# Ingresso_1_1SchDoc.net
KiCad netlist of a schematic drawn in Altium Designer
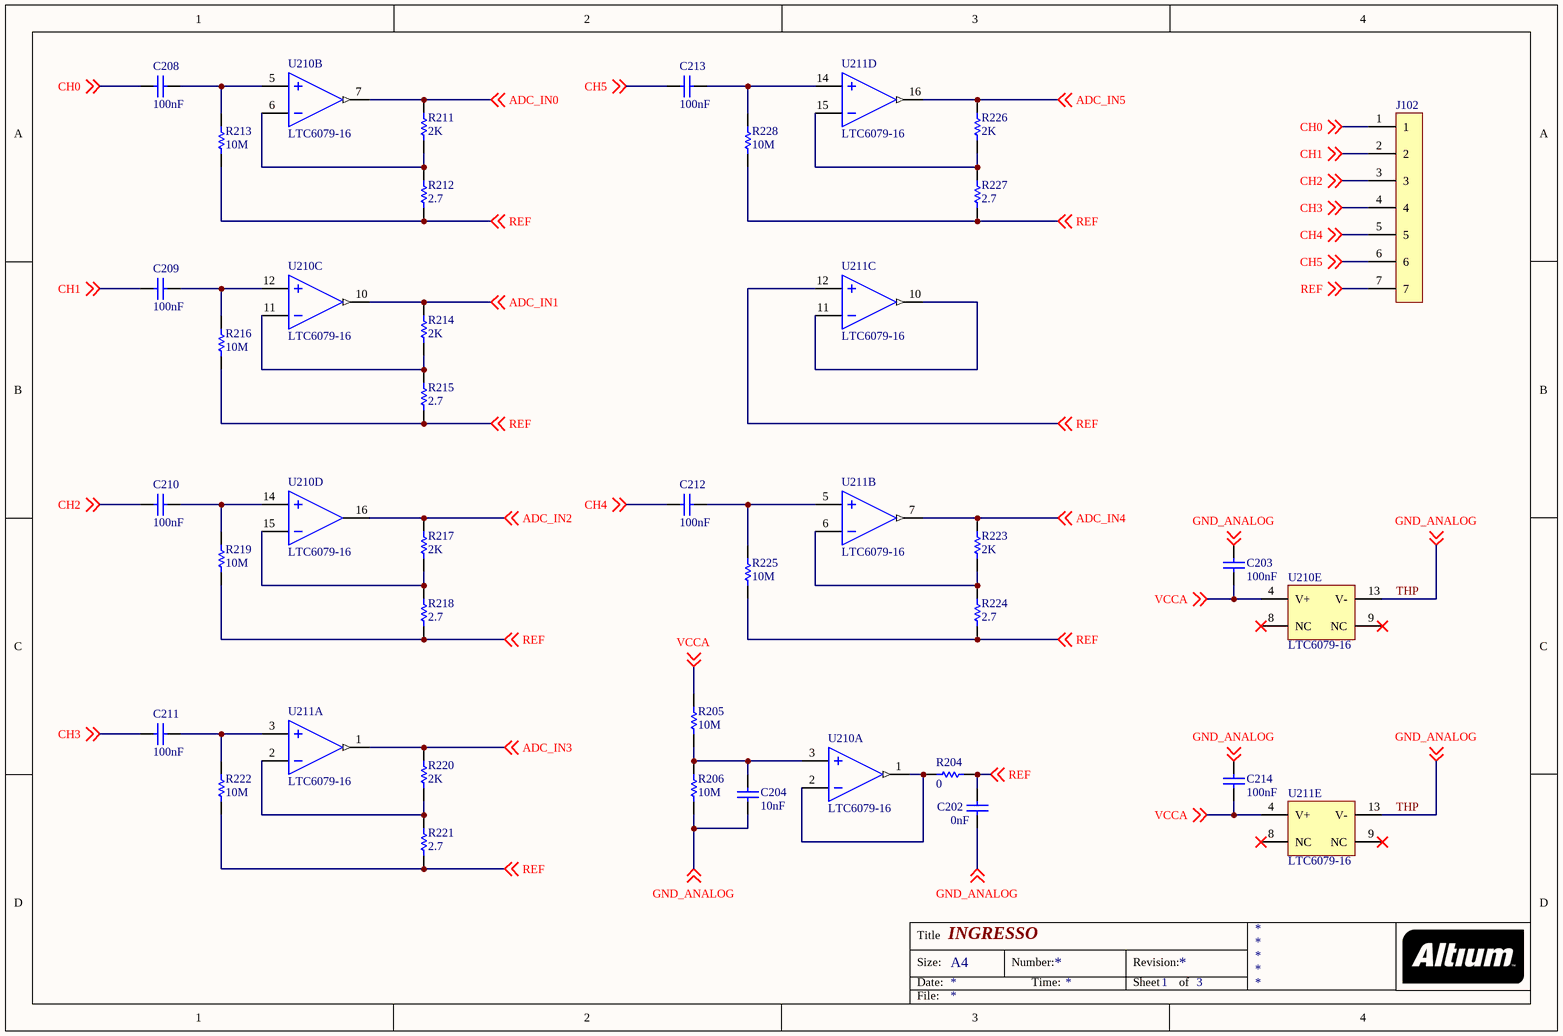
[diagram p0: Ingresso_1.1SchDoc.SchDoc]

(export (version "E")
  (design (tool "Eeschema 10.0.6"))
  (components
    (comp (ref "C202")
      (value "0nF")
      (footprint "Footprint:0402 Capacitor")
      (description "Capacitor SMD 0402")
      (fields
        (field (name "MANUFACTURER") "MULTICOMP")
        (field (name "MANUFACTURER PART NUMBER") "MC0402X104M160CT")
        (field (name "PUBLISHER") "Altium Limited")
      )
      (libsource (lib "Capacitor") (part "Cap SMD"))
    )
    (comp (ref "C203")
      (value "100nF")
      (footprint "Footprint:0402 Capacitor")
      (description "Capacitor SMD 0402")
      (fields
        (field (name "MANUFACTURER") "MULTICOMP")
        (field (name "MANUFACTURER PART NUMBER") "MC0402X104M160CT")
        (field (name "PUBLISHER") "Altium Limited")
      )
      (libsource (lib "Capacitor") (part "Cap SMD"))
    )
    (comp (ref "C204")
      (value "10nF")
      (footprint "Footprint:0402 Capacitor")
      (description "Capacitor SMD 0402")
      (fields
        (field (name "MANUFACTURER") "MULTICOMP")
        (field (name "MANUFACTURER PART NUMBER") "MC0402X104M160CT")
        (field (name "PUBLISHER") "Altium Limited")
      )
      (libsource (lib "Capacitor") (part "Cap SMD"))
    )
    (comp (ref "C208")
      (value "100nF")
      (footprint "Footprint:0402 Capacitor")
      (description "Capacitor SMD 0402")
      (fields
        (field (name "MANUFACTURER") "MULTICOMP")
        (field (name "MANUFACTURER PART NUMBER") "MC0402X104M160CT")
        (field (name "PUBLISHER") "Altium Limited")
      )
      (libsource (lib "Capacitor") (part "Cap SMD"))
    )
    (comp (ref "C209")
      (value "100nF")
      (footprint "Footprint:0402 Capacitor")
      (description "Capacitor SMD 0402")
      (fields
        (field (name "MANUFACTURER") "MULTICOMP")
        (field (name "MANUFACTURER PART NUMBER") "MC0402X104M160CT")
        (field (name "PUBLISHER") "Altium Limited")
      )
      (libsource (lib "Capacitor") (part "Cap SMD"))
    )
    (comp (ref "C210")
      (value "100nF")
      (footprint "Footprint:0402 Capacitor")
      (description "Capacitor SMD 0402")
      (fields
        (field (name "MANUFACTURER") "MULTICOMP")
        (field (name "MANUFACTURER PART NUMBER") "MC0402X104M160CT")
        (field (name "PUBLISHER") "Altium Limited")
      )
      (libsource (lib "Capacitor") (part "Cap SMD"))
    )
    (comp (ref "C211")
      (value "100nF")
      (footprint "Footprint:0402 Capacitor")
      (description "Capacitor SMD 0402")
      (fields
        (field (name "MANUFACTURER") "MULTICOMP")
        (field (name "MANUFACTURER PART NUMBER") "MC0402X104M160CT")
        (field (name "PUBLISHER") "Altium Limited")
      )
      (libsource (lib "Capacitor") (part "Cap SMD"))
    )
    (comp (ref "C212")
      (value "100nF")
      (footprint "Footprint:0402 Capacitor")
      (description "Capacitor SMD 0402")
      (fields
        (field (name "MANUFACTURER") "MULTICOMP")
        (field (name "MANUFACTURER PART NUMBER") "MC0402X104M160CT")
        (field (name "PUBLISHER") "Altium Limited")
      )
      (libsource (lib "Capacitor") (part "Cap SMD"))
    )
    (comp (ref "C213")
      (value "100nF")
      (footprint "Footprint:0402 Capacitor")
      (description "Capacitor SMD 0402")
      (fields
        (field (name "MANUFACTURER") "MULTICOMP")
        (field (name "MANUFACTURER PART NUMBER") "MC0402X104M160CT")
        (field (name "PUBLISHER") "Altium Limited")
      )
      (libsource (lib "Capacitor") (part "Cap SMD"))
    )
    (comp (ref "C214")
      (value "100nF")
      (footprint "Footprint:0402 Capacitor")
      (description "Capacitor SMD 0402")
      (fields
        (field (name "MANUFACTURER") "MULTICOMP")
        (field (name "MANUFACTURER PART NUMBER") "MC0402X104M160CT")
        (field (name "PUBLISHER") "Altium Limited")
      )
      (libsource (lib "Capacitor") (part "Cap SMD"))
    )
    (comp (ref "J102")
      (value "HEADER 1X7")
      (footprint "Footprint:HEADER 1X7")
      (description "Inductor")
      (fields (field (name "PUBLISHER") "Altium Limited"))
      (libsource (lib "Connector") (part "HEADER 1X7"))
    )
    (comp (ref "R204")
      (value "0")
      (footprint "Footprint:0402 resistor")
      (description "Resistor SMD 0402")
      (fields
        (field (name "MANUFACTURER") "MULTICOMP")
        (field (name "MANUFACTURER PART NUMBER") "MC00625W040212K")
      )
      (libsource (lib "resistor") (part "RSMD"))
    )
    (comp (ref "R205")
      (value "10M")
      (footprint "Footprint:0402 resistor")
      (description "Resistor SMD 0402")
      (fields
        (field (name "MANUFACTURER") "MULTICOMP")
        (field (name "MANUFACTURER PART NUMBER") "MC00625W040212K")
      )
      (libsource (lib "resistor") (part "RSMD"))
    )
    (comp (ref "R206")
      (value "10M")
      (footprint "Footprint:0402 resistor")
      (description "Resistor SMD 0402")
      (fields
        (field (name "MANUFACTURER") "MULTICOMP")
        (field (name "MANUFACTURER PART NUMBER") "MC00625W040212K")
      )
      (libsource (lib "resistor") (part "RSMD"))
    )
    (comp (ref "R211")
      (value "2K")
      (footprint "Footprint:0402 resistor")
      (description "Resistor SMD 0402")
      (fields
        (field (name "MANUFACTURER") "MULTICOMP")
        (field (name "MANUFACTURER PART NUMBER") "MC00625W040212K")
      )
      (libsource (lib "resistor") (part "RSMD"))
    )
    (comp (ref "R212")
      (value "2.7")
      (footprint "Footprint:0402 resistor")
      (description "Resistor SMD 0402")
      (fields
        (field (name "MANUFACTURER") "MULTICOMP")
        (field (name "MANUFACTURER PART NUMBER") "MC00625W040212K")
      )
      (libsource (lib "resistor") (part "RSMD"))
    )
    (comp (ref "R213")
      (value "10M")
      (footprint "Footprint:0402 resistor")
      (description "Resistor SMD 0402")
      (fields
        (field (name "MANUFACTURER") "MULTICOMP")
        (field (name "MANUFACTURER PART NUMBER") "MC00625W040212K")
      )
      (libsource (lib "resistor") (part "RSMD"))
    )
    (comp (ref "R214")
      (value "2K")
      (footprint "Footprint:0402 resistor")
      (description "Resistor SMD 0402")
      (fields
        (field (name "MANUFACTURER") "MULTICOMP")
        (field (name "MANUFACTURER PART NUMBER") "MC00625W040212K")
      )
      (libsource (lib "resistor") (part "RSMD"))
    )
    (comp (ref "R215")
      (value "2.7")
      (footprint "Footprint:0402 resistor")
      (description "Resistor SMD 0402")
      (fields
        (field (name "MANUFACTURER") "MULTICOMP")
        (field (name "MANUFACTURER PART NUMBER") "MC00625W040212K")
      )
      (libsource (lib "resistor") (part "RSMD"))
    )
    (comp (ref "R216")
      (value "10M")
      (footprint "Footprint:0402 resistor")
      (description "Resistor SMD 0402")
      (fields
        (field (name "MANUFACTURER") "MULTICOMP")
        (field (name "MANUFACTURER PART NUMBER") "MC00625W040212K")
      )
      (libsource (lib "resistor") (part "RSMD"))
    )
    (comp (ref "R217")
      (value "2K")
      (footprint "Footprint:0402 resistor")
      (description "Resistor SMD 0402")
      (fields
        (field (name "MANUFACTURER") "MULTICOMP")
        (field (name "MANUFACTURER PART NUMBER") "MC00625W040212K")
      )
      (libsource (lib "resistor") (part "RSMD"))
    )
    (comp (ref "R218")
      (value "2.7")
      (footprint "Footprint:0402 resistor")
      (description "Resistor SMD 0402")
      (fields
        (field (name "MANUFACTURER") "MULTICOMP")
        (field (name "MANUFACTURER PART NUMBER") "MC00625W040212K")
      )
      (libsource (lib "resistor") (part "RSMD"))
    )
    (comp (ref "R219")
      (value "10M")
      (footprint "Footprint:0402 resistor")
      (description "Resistor SMD 0402")
      (fields
        (field (name "MANUFACTURER") "MULTICOMP")
        (field (name "MANUFACTURER PART NUMBER") "MC00625W040212K")
      )
      (libsource (lib "resistor") (part "RSMD"))
    )
    (comp (ref "R220")
      (value "2K")
      (footprint "Footprint:0402 resistor")
      (description "Resistor SMD 0402")
      (fields
        (field (name "MANUFACTURER") "MULTICOMP")
        (field (name "MANUFACTURER PART NUMBER") "MC00625W040212K")
      )
      (libsource (lib "resistor") (part "RSMD"))
    )
    (comp (ref "R221")
      (value "2.7")
      (footprint "Footprint:0402 resistor")
      (description "Resistor SMD 0402")
      (fields
        (field (name "MANUFACTURER") "MULTICOMP")
        (field (name "MANUFACTURER PART NUMBER") "MC00625W040212K")
      )
      (libsource (lib "resistor") (part "RSMD"))
    )
    (comp (ref "R222")
      (value "10M")
      (footprint "Footprint:0402 resistor")
      (description "Resistor SMD 0402")
      (fields
        (field (name "MANUFACTURER") "MULTICOMP")
        (field (name "MANUFACTURER PART NUMBER") "MC00625W040212K")
      )
      (libsource (lib "resistor") (part "RSMD"))
    )
    (comp (ref "R223")
      (value "2K")
      (footprint "Footprint:0402 resistor")
      (description "Resistor SMD 0402")
      (fields
        (field (name "MANUFACTURER") "MULTICOMP")
        (field (name "MANUFACTURER PART NUMBER") "MC00625W040212K")
      )
      (libsource (lib "resistor") (part "RSMD"))
    )
    (comp (ref "R224")
      (value "2.7")
      (footprint "Footprint:0402 resistor")
      (description "Resistor SMD 0402")
      (fields
        (field (name "MANUFACTURER") "MULTICOMP")
        (field (name "MANUFACTURER PART NUMBER") "MC00625W040212K")
      )
      (libsource (lib "resistor") (part "RSMD"))
    )
    (comp (ref "R225")
      (value "10M")
      (footprint "Footprint:0402 resistor")
      (description "Resistor SMD 0402")
      (fields
        (field (name "MANUFACTURER") "MULTICOMP")
        (field (name "MANUFACTURER PART NUMBER") "MC00625W040212K")
      )
      (libsource (lib "resistor") (part "RSMD"))
    )
    (comp (ref "R226")
      (value "2K")
      (footprint "Footprint:0402 resistor")
      (description "Resistor SMD 0402")
      (fields
        (field (name "MANUFACTURER") "MULTICOMP")
        (field (name "MANUFACTURER PART NUMBER") "MC00625W040212K")
      )
      (libsource (lib "resistor") (part "RSMD"))
    )
    (comp (ref "R227")
      (value "2.7")
      (footprint "Footprint:0402 resistor")
      (description "Resistor SMD 0402")
      (fields
        (field (name "MANUFACTURER") "MULTICOMP")
        (field (name "MANUFACTURER PART NUMBER") "MC00625W040212K")
      )
      (libsource (lib "resistor") (part "RSMD"))
    )
    (comp (ref "R228")
      (value "10M")
      (footprint "Footprint:0402 resistor")
      (description "Resistor SMD 0402")
      (fields
        (field (name "MANUFACTURER") "MULTICOMP")
        (field (name "MANUFACTURER PART NUMBER") "MC00625W040212K")
      )
      (libsource (lib "resistor") (part "RSMD"))
    )
    (comp (ref "U210")
      (value "LTC6079-16")
      (footprint "Footprint:LTC6079DHC")
      (libsource (lib "LT-LTC608X-LTC607X-16") (part "LT-LTC608X-LTC607X-16"))
    )
    (comp (ref "U211")
      (value "LTC6079-16")
      (footprint "Footprint:LTC6079DHC")
      (libsource (lib "LT-LTC608X-LTC607X-16") (part "LT-LTC608X-LTC607X-16"))
    )
  )
  (nets
    (net (code "1") (name "ADC_IN0") (class "Default")
      (node (ref "R211") (pin "2") (pinfunction "2_2") (pintype "passive"))
      (node (ref "U210") (pin "7") (pinfunction "OUT_B_7") (pintype "output"))
    )
    (net (code "2") (name "ADC_IN1") (class "Default")
      (node (ref "R214") (pin "2") (pinfunction "2_2") (pintype "passive"))
      (node (ref "U210") (pin "10") (pinfunction "OUT_C_10") (pintype "output"))
    )
    (net (code "3") (name "ADC_IN2") (class "Default")
      (node (ref "R217") (pin "2") (pinfunction "2_2") (pintype "passive"))
      (node (ref "U210") (pin "16") (pinfunction "OUT_D_16") (pintype "output"))
    )
    (net (code "4") (name "ADC_IN3") (class "Default")
      (node (ref "R220") (pin "2") (pinfunction "2_2") (pintype "passive"))
      (node (ref "U211") (pin "1") (pinfunction "OUT_A_1") (pintype "output"))
    )
    (net (code "5") (name "ADC_IN4") (class "Default")
      (node (ref "R223") (pin "2") (pinfunction "2_2") (pintype "passive"))
      (node (ref "U211") (pin "7") (pinfunction "OUT_B_7") (pintype "output"))
    )
    (net (code "6") (name "ADC_IN5") (class "Default")
      (node (ref "R226") (pin "2") (pinfunction "2_2") (pintype "passive"))
      (node (ref "U211") (pin "16") (pinfunction "OUT_D_16") (pintype "output"))
    )
    (net (code "7") (name "CH0") (class "Default")
      (node (ref "C208") (pin "1") (pinfunction "1_1") (pintype "passive"))
      (node (ref "J102") (pin "1") (pinfunction "1_1") (pintype "passive"))
    )
    (net (code "8") (name "CH1") (class "Default")
      (node (ref "C209") (pin "1") (pinfunction "1_1") (pintype "passive"))
      (node (ref "J102") (pin "2") (pinfunction "2_2") (pintype "passive"))
    )
    (net (code "9") (name "CH2") (class "Default")
      (node (ref "C210") (pin "1") (pinfunction "1_1") (pintype "passive"))
      (node (ref "J102") (pin "3") (pinfunction "3_3") (pintype "passive"))
    )
    (net (code "10") (name "CH3") (class "Default")
      (node (ref "C211") (pin "1") (pinfunction "1_1") (pintype "passive"))
      (node (ref "J102") (pin "4") (pinfunction "4_4") (pintype "passive"))
    )
    (net (code "11") (name "CH4") (class "Default")
      (node (ref "C212") (pin "1") (pinfunction "1_1") (pintype "passive"))
      (node (ref "J102") (pin "5") (pinfunction "5_5") (pintype "passive"))
    )
    (net (code "12") (name "CH5") (class "Default")
      (node (ref "C213") (pin "1") (pinfunction "1_1") (pintype "passive"))
      (node (ref "J102") (pin "6") (pinfunction "6_6") (pintype "passive"))
    )
    (net (code "13") (name "GND_ANALOG") (class "Default")
      (node (ref "C202") (pin "1") (pinfunction "1_1") (pintype "passive"))
      (node (ref "C203") (pin "2") (pinfunction "2_2") (pintype "passive"))
      (node (ref "C204") (pin "1") (pinfunction "1_1") (pintype "passive"))
      (node (ref "C214") (pin "2") (pinfunction "2_2") (pintype "passive"))
      (node (ref "R206") (pin "1") (pinfunction "1_1") (pintype "passive"))
      (node (ref "U210") (pin "13") (pinfunction "V-_13") (pintype "power_in"))
      (node (ref "U211") (pin "13") (pinfunction "V-_13") (pintype "power_in"))
    )
    (net (code "14") (name "Net-(U210A-IN+_A)") (class "Default")
      (node (ref "C204") (pin "2") (pinfunction "2_2") (pintype "passive"))
      (node (ref "R205") (pin "1") (pinfunction "1_1") (pintype "passive"))
      (node (ref "R206") (pin "2") (pinfunction "2_2") (pintype "passive"))
      (node (ref "U210") (pin "3") (pinfunction "IN+_A_3") (pintype "input"))
    )
    (net (code "15") (name "Net-(U210A-IN-_A)") (class "Default")
      (node (ref "R204") (pin "1") (pinfunction "1_1") (pintype "passive"))
      (node (ref "U210") (pin "1") (pinfunction "OUT_A_1") (pintype "output"))
      (node (ref "U210") (pin "2") (pinfunction "IN-_A_2") (pintype "input"))
    )
    (net (code "16") (name "Net-(U210B-IN+_B)") (class "Default")
      (node (ref "C208") (pin "2") (pinfunction "2_2") (pintype "passive"))
      (node (ref "R213") (pin "2") (pinfunction "2_2") (pintype "passive"))
      (node (ref "U210") (pin "5") (pinfunction "IN+_B_5") (pintype "input"))
    )
    (net (code "17") (name "Net-(U210B-IN-_B)") (class "Default")
      (node (ref "R211") (pin "1") (pinfunction "1_1") (pintype "passive"))
      (node (ref "R212") (pin "2") (pinfunction "2_2") (pintype "passive"))
      (node (ref "U210") (pin "6") (pinfunction "IN-_B_6") (pintype "input"))
    )
    (net (code "18") (name "Net-(U210C-IN+_C)") (class "Default")
      (node (ref "C209") (pin "2") (pinfunction "2_2") (pintype "passive"))
      (node (ref "R216") (pin "2") (pinfunction "2_2") (pintype "passive"))
      (node (ref "U210") (pin "12") (pinfunction "IN+_C_12") (pintype "input"))
    )
    (net (code "19") (name "Net-(U210C-IN-_C)") (class "Default")
      (node (ref "R214") (pin "1") (pinfunction "1_1") (pintype "passive"))
      (node (ref "R215") (pin "2") (pinfunction "2_2") (pintype "passive"))
      (node (ref "U210") (pin "11") (pinfunction "IN-_C_11") (pintype "input"))
    )
    (net (code "20") (name "Net-(U210D-IN+_D)") (class "Default")
      (node (ref "C210") (pin "2") (pinfunction "2_2") (pintype "passive"))
      (node (ref "R219") (pin "2") (pinfunction "2_2") (pintype "passive"))
      (node (ref "U210") (pin "14") (pinfunction "IN+_D_14") (pintype "passive"))
    )
    (net (code "21") (name "Net-(U210D-IN-_D)") (class "Default")
      (node (ref "R217") (pin "1") (pinfunction "1_1") (pintype "passive"))
      (node (ref "R218") (pin "2") (pinfunction "2_2") (pintype "passive"))
      (node (ref "U210") (pin "15") (pinfunction "IN-_D_15") (pintype "passive"))
    )
    (net (code "22") (name "Net-(U211A-IN+_A)") (class "Default")
      (node (ref "C211") (pin "2") (pinfunction "2_2") (pintype "passive"))
      (node (ref "R222") (pin "2") (pinfunction "2_2") (pintype "passive"))
      (node (ref "U211") (pin "3") (pinfunction "IN+_A_3") (pintype "input"))
    )
    (net (code "23") (name "Net-(U211A-IN-_A)") (class "Default")
      (node (ref "R220") (pin "1") (pinfunction "1_1") (pintype "passive"))
      (node (ref "R221") (pin "1") (pinfunction "1_1") (pintype "passive"))
      (node (ref "U211") (pin "2") (pinfunction "IN-_A_2") (pintype "input"))
    )
    (net (code "24") (name "Net-(U211B-IN+_B)") (class "Default")
      (node (ref "C212") (pin "2") (pinfunction "2_2") (pintype "passive"))
      (node (ref "R225") (pin "2") (pinfunction "2_2") (pintype "passive"))
      (node (ref "U211") (pin "5") (pinfunction "IN+_B_5") (pintype "input"))
    )
    (net (code "25") (name "Net-(U211B-IN-_B)") (class "Default")
      (node (ref "R223") (pin "1") (pinfunction "1_1") (pintype "passive"))
      (node (ref "R224") (pin "2") (pinfunction "2_2") (pintype "passive"))
      (node (ref "U211") (pin "6") (pinfunction "IN-_B_6") (pintype "input"))
    )
    (net (code "26") (name "Net-(U211C-IN-_C)") (class "Default")
      (node (ref "U211") (pin "10") (pinfunction "OUT_C_10") (pintype "output"))
      (node (ref "U211") (pin "11") (pinfunction "IN-_C_11") (pintype "input"))
    )
    (net (code "27") (name "Net-(U211D-IN+_D)") (class "Default")
      (node (ref "C213") (pin "2") (pinfunction "2_2") (pintype "passive"))
      (node (ref "R228") (pin "2") (pinfunction "2_2") (pintype "passive"))
      (node (ref "U211") (pin "14") (pinfunction "IN+_D_14") (pintype "passive"))
    )
    (net (code "28") (name "Net-(U211D-IN-_D)") (class "Default")
      (node (ref "R226") (pin "1") (pinfunction "1_1") (pintype "passive"))
      (node (ref "R227") (pin "2") (pinfunction "2_2") (pintype "passive"))
      (node (ref "U211") (pin "15") (pinfunction "IN-_D_15") (pintype "passive"))
    )
    (net (code "29") (name "REF") (class "Default")
      (node (ref "C202") (pin "2") (pinfunction "2_2") (pintype "passive"))
      (node (ref "J102") (pin "7") (pinfunction "7_7") (pintype "passive"))
      (node (ref "R204") (pin "2") (pinfunction "2_2") (pintype "passive"))
      (node (ref "R212") (pin "1") (pinfunction "1_1") (pintype "passive"))
      (node (ref "R213") (pin "1") (pinfunction "1_1") (pintype "passive"))
      (node (ref "R215") (pin "1") (pinfunction "1_1") (pintype "passive"))
      (node (ref "R216") (pin "1") (pinfunction "1_1") (pintype "passive"))
      (node (ref "R218") (pin "1") (pinfunction "1_1") (pintype "passive"))
      (node (ref "R219") (pin "1") (pinfunction "1_1") (pintype "passive"))
      (node (ref "R221") (pin "2") (pinfunction "2_2") (pintype "passive"))
      (node (ref "R222") (pin "1") (pinfunction "1_1") (pintype "passive"))
      (node (ref "R224") (pin "1") (pinfunction "1_1") (pintype "passive"))
      (node (ref "R225") (pin "1") (pinfunction "1_1") (pintype "passive"))
      (node (ref "R227") (pin "1") (pinfunction "1_1") (pintype "passive"))
      (node (ref "R228") (pin "1") (pinfunction "1_1") (pintype "passive"))
      (node (ref "U211") (pin "12") (pinfunction "IN+_C_12") (pintype "input"))
    )
    (net (code "30") (name "VCCA") (class "Default")
      (node (ref "C203") (pin "1") (pinfunction "1_1") (pintype "passive"))
      (node (ref "C214") (pin "1") (pinfunction "1_1") (pintype "passive"))
      (node (ref "R205") (pin "2") (pinfunction "2_2") (pintype "passive"))
      (node (ref "U210") (pin "4") (pinfunction "V+_4") (pintype "power_in"))
      (node (ref "U211") (pin "4") (pinfunction "V+_4") (pintype "power_in"))
    )
    (net (code "31") (name "unconnected-(U210E-NC-Pad8)") (class "Default")
      (node (ref "U210") (pin "8") (pinfunction "NC_8") (pintype "passive+no_connect"))
    )
    (net (code "32") (name "unconnected-(U210E-NC-Pad9)") (class "Default")
      (node (ref "U210") (pin "9") (pinfunction "NC_9") (pintype "passive+no_connect"))
    )
    (net (code "33") (name "unconnected-(U211E-NC-Pad8)") (class "Default")
      (node (ref "U211") (pin "8") (pinfunction "NC_8") (pintype "passive+no_connect"))
    )
    (net (code "34") (name "unconnected-(U211E-NC-Pad9)") (class "Default")
      (node (ref "U211") (pin "9") (pinfunction "NC_9") (pintype "passive+no_connect"))
    )
  )
)
